# Bare_ESP32.net
KiCad netlist of a schematic drawn in EAGLE
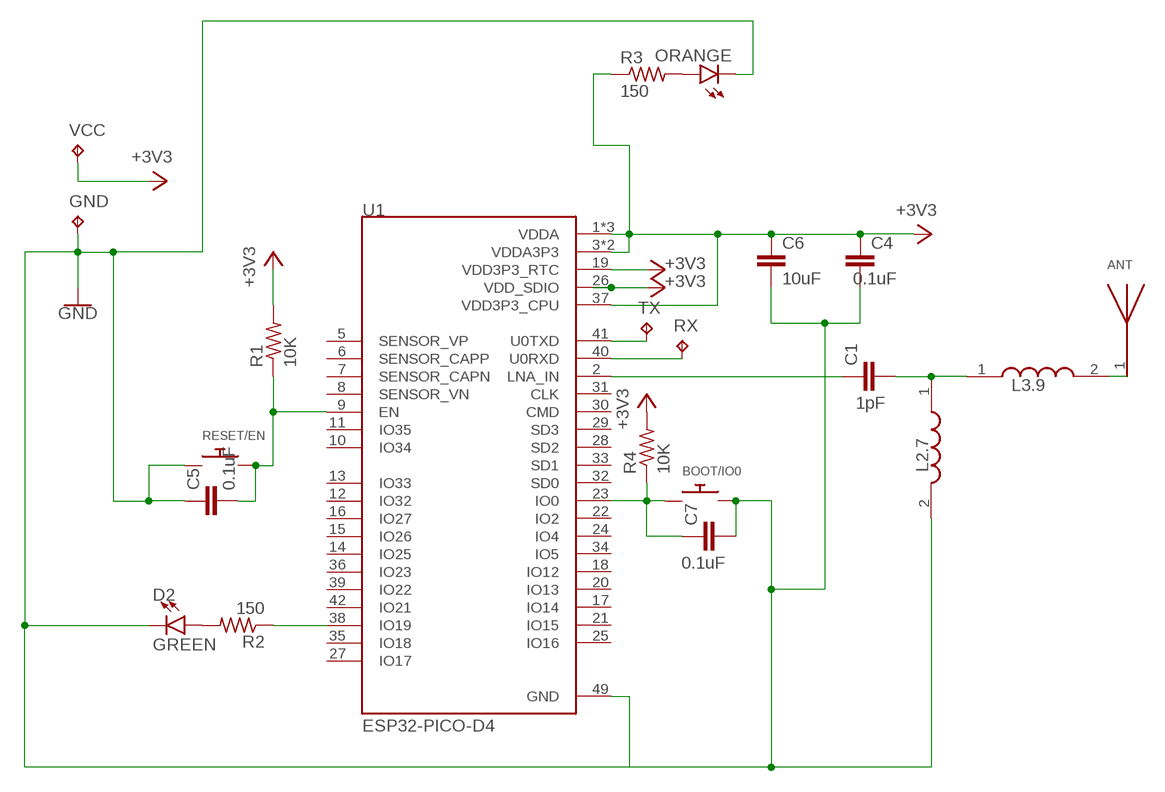
[diagram p0: schematic, sheet 1]

(export (version "E")
  (design (tool "Eeschema 10.0.6"))
  (components
    (comp (ref "ANT")
      (value "2450AT18A100E")
      (footprint "eagle-import:ANTC3216X140N")
      (fields (field (name "MF") "Johanson Technology"))
      (libsource (lib "eagle-import") (part "2450AT18A100E"))
    )
    (comp (ref "BOOT/IO0")
      (value "SWITCH_PUSHBUTTONEVQ-PE")
      (footprint "eagle-import:TACT_PANA-EVQ")
      (libsource (lib "eagle-import") (part "SWITCH_PUSHBUTTONEVQ-PE"))
    )
    (comp (ref "C1")
      (value "1pF")
      (footprint "eagle-import:0402")
      (libsource (lib "eagle-import") (part "0.1UF-0402-16V-10%"))
    )
    (comp (ref "C4")
      (value "0.1uF")
      (footprint "eagle-import:0402")
      (libsource (lib "eagle-import") (part "0.1UF-0402-16V-10%"))
    )
    (comp (ref "C5")
      (value "0.1uF")
      (footprint "eagle-import:0402")
      (libsource (lib "eagle-import") (part "0.1UF-0402-16V-10%"))
    )
    (comp (ref "C6")
      (value "10uF")
      (footprint "eagle-import:0402")
      (libsource (lib "eagle-import") (part "0.1UF-0402-16V-10%"))
    )
    (comp (ref "C7")
      (value "0.1uF")
      (footprint "eagle-import:0402")
      (libsource (lib "eagle-import") (part "0.1UF-0402-16V-10%"))
    )
    (comp (ref "D2")
      (value "GREEN")
      (footprint "eagle-import:LED-1206")
      (libsource (lib "eagle-import") (part "LED-GREEN1206"))
    )
    (comp (ref "GND")
      (value "TPTP14SQ")
      (footprint "eagle-import:TP14SQ")
      (libsource (lib "eagle-import") (part "TPTP14SQ"))
    )
    (comp (ref "L2.7")
      (value "2.7nH")
      (footprint "eagle-import:INDC1005X60N")
      (fields
        (field (name "MANUFACTURER_PART_NUMBER") "L-07C2N7SV6T")
        (field (name "MOUSER_PART_NUMBER") "609-L-07C2N7SV6T")
      )
      (libsource (lib "eagle-import") (part "L-07C2N7SV6T"))
    )
    (comp (ref "L3.9")
      (value "3.9nH")
      (footprint "eagle-import:INDC1005X60N")
      (fields
        (field (name "MANUFACTURER_PART_NUMBER") "L-07C2N7SV6T")
        (field (name "MOUSER_PART_NUMBER") "609-L-07C2N7SV6T")
      )
      (libsource (lib "eagle-import") (part "L-07C2N7SV6T"))
    )
    (comp (ref "ORANGE")
      (value "LED-ORANGE0603")
      (footprint "eagle-import:0603-ORANGE")
      (libsource (lib "eagle-import") (part "LED-ORANGE0603"))
    )
    (comp (ref "R1")
      (value "10K")
      (footprint "eagle-import:R0402")
      (libsource (lib "eagle-import") (part "R-US_R0402"))
    )
    (comp (ref "R2")
      (value "150")
      (footprint "eagle-import:R0402")
      (libsource (lib "eagle-import") (part "R-US_R0402"))
    )
    (comp (ref "R3")
      (value "150")
      (footprint "eagle-import:R0402")
      (libsource (lib "eagle-import") (part "R-US_R0402"))
    )
    (comp (ref "R4")
      (value "10K")
      (footprint "eagle-import:R0402")
      (libsource (lib "eagle-import") (part "R-US_R0402"))
    )
    (comp (ref "RESET/EN")
      (value "SWITCH_PUSHBUTTONEVQ-PE")
      (footprint "eagle-import:TACT_PANA-EVQ")
      (libsource (lib "eagle-import") (part "SWITCH_PUSHBUTTONEVQ-PE"))
    )
    (comp (ref "RX")
      (value "TPTP14SQ")
      (footprint "eagle-import:TP14SQ")
      (libsource (lib "eagle-import") (part "TPTP14SQ"))
    )
    (comp (ref "TX")
      (value "TPTP14SQ")
      (footprint "eagle-import:TP14SQ")
      (libsource (lib "eagle-import") (part "TPTP14SQ"))
    )
    (comp (ref "U1")
      (value "ESP32-PICO-D4")
      (footprint "eagle-import:PQFN50P700X700X104-49N")
      (fields (field (name "MF") "Espressif Systems"))
      (libsource (lib "eagle-import") (part "ESP32-PICO-D4"))
    )
    (comp (ref "VCC")
      (value "TPTP14SQ")
      (footprint "eagle-import:TP14SQ")
      (libsource (lib "eagle-import") (part "TPTP14SQ"))
    )
  )
  (nets
    (net (code "1") (name "+3V3") (class "Default")
      (node (ref "C4") (pin "1") (pinfunction "1_1") (pintype "passive"))
      (node (ref "C6") (pin "1") (pinfunction "1_1") (pintype "passive"))
      (node (ref "R1") (pin "2") (pinfunction "2_2") (pintype "passive"))
      (node (ref "R3") (pin "1") (pinfunction "1_1") (pintype "passive"))
      (node (ref "R4") (pin "2") (pinfunction "2_2") (pintype "passive"))
      (node (ref "U1") (pin "1") (pinfunction "VDDA_1") (pintype "power_in"))
      (node (ref "U1") (pin "19") (pinfunction "VDD3P3_RTC_19") (pintype "power_in"))
      (node (ref "U1") (pin "26") (pinfunction "VDD_SDIO_26") (pintype "power_in"))
      (node (ref "U1") (pin "3") (pinfunction "VDDA3P3_3") (pintype "power_in"))
      (node (ref "U1") (pin "37") (pinfunction "VDD3P3_CPU_37") (pintype "power_in"))
      (node (ref "U1") (pin "4") (pinfunction "VDDA3P3_4") (pintype "power_in"))
      (node (ref "U1") (pin "43") (pinfunction "VDDA_43") (pintype "power_in"))
      (node (ref "U1") (pin "46") (pinfunction "VDDA_46") (pintype "power_in"))
      (node (ref "VCC") (pin "TP") (pinfunction "TP_TP") (pintype "input"))
    )
    (net (code "2") (name "GND") (class "Default")
      (node (ref "BOOT/IO0") (pin "P$2") (pinfunction "P$2_P$2") (pintype "passive"))
      (node (ref "C4") (pin "2") (pinfunction "2_2") (pintype "passive"))
      (node (ref "C5") (pin "1") (pinfunction "1_1") (pintype "passive"))
      (node (ref "C6") (pin "2") (pinfunction "2_2") (pintype "passive"))
      (node (ref "C7") (pin "2") (pinfunction "2_2") (pintype "passive"))
      (node (ref "D2") (pin "C") (pinfunction "C_C") (pintype "passive"))
      (node (ref "GND") (pin "TP") (pinfunction "TP_TP") (pintype "input"))
      (node (ref "L2.7") (pin "2") (pinfunction "2_2") (pintype "bidirectional"))
      (node (ref "ORANGE") (pin "C") (pinfunction "C_C") (pintype "passive"))
      (node (ref "RESET/EN") (pin "P$1") (pinfunction "P$1_P$1") (pintype "passive"))
      (node (ref "U1") (pin "49") (pinfunction "GND_49") (pintype "power_in"))
    )
    (net (code "3") (name "Net-(ANT-Pad1)") (class "Default")
      (node (ref "ANT") (pin "1") (pinfunction "1_1") (pintype "input"))
      (node (ref "L3.9") (pin "2") (pinfunction "2_2") (pintype "bidirectional"))
    )
    (net (code "4") (name "Net-(C1-Pad2)") (class "Default")
      (node (ref "C1") (pin "2") (pinfunction "2_2") (pintype "passive"))
      (node (ref "L2.7") (pin "1") (pinfunction "1_1") (pintype "bidirectional"))
      (node (ref "L3.9") (pin "1") (pinfunction "1_1") (pintype "bidirectional"))
    )
    (net (code "5") (name "Net-(D2-PadA)") (class "Default")
      (node (ref "D2") (pin "A") (pinfunction "A_A") (pintype "passive"))
      (node (ref "R2") (pin "2") (pinfunction "2_2") (pintype "passive"))
    )
    (net (code "6") (name "Net-(ORANGE-PadA)") (class "Default")
      (node (ref "ORANGE") (pin "A") (pinfunction "A_A") (pintype "passive"))
      (node (ref "R3") (pin "2") (pinfunction "2_2") (pintype "passive"))
    )
    (net (code "7") (name "Net-(U1-EN)") (class "Default")
      (node (ref "C5") (pin "2") (pinfunction "2_2") (pintype "passive"))
      (node (ref "R1") (pin "1") (pinfunction "1_1") (pintype "passive"))
      (node (ref "RESET/EN") (pin "P$2") (pinfunction "P$2_P$2") (pintype "passive"))
      (node (ref "U1") (pin "9") (pinfunction "EN_9") (pintype "input"))
    )
    (net (code "8") (name "Net-(U1-IO0)") (class "Default")
      (node (ref "BOOT/IO0") (pin "P$1") (pinfunction "P$1_P$1") (pintype "passive"))
      (node (ref "C7") (pin "1") (pinfunction "1_1") (pintype "passive"))
      (node (ref "R4") (pin "1") (pinfunction "1_1") (pintype "passive"))
      (node (ref "U1") (pin "23") (pinfunction "IO0_23") (pintype "bidirectional"))
    )
    (net (code "9") (name "Net-(U1-IO19)") (class "Default")
      (node (ref "R2") (pin "1") (pinfunction "1_1") (pintype "passive"))
      (node (ref "U1") (pin "38") (pinfunction "IO19_38") (pintype "bidirectional"))
    )
    (net (code "10") (name "Net-(U1-LNA_IN)") (class "Default")
      (node (ref "C1") (pin "1") (pinfunction "1_1") (pintype "passive"))
      (node (ref "U1") (pin "2") (pinfunction "LNA_IN_2") (pintype "bidirectional"))
    )
    (net (code "11") (name "Net-(U1-U0RXD)") (class "Default")
      (node (ref "RX") (pin "TP") (pinfunction "TP_TP") (pintype "input"))
      (node (ref "U1") (pin "40") (pinfunction "U0RXD_40") (pintype "bidirectional"))
    )
    (net (code "12") (name "Net-(U1-U0TXD)") (class "Default")
      (node (ref "TX") (pin "TP") (pinfunction "TP_TP") (pintype "input"))
      (node (ref "U1") (pin "41") (pinfunction "U0TXD_41") (pintype "bidirectional"))
    )
    (net (code "13") (name "unconnected-(U1-CLK-Pad31)") (class "Default")
      (node (ref "U1") (pin "31") (pinfunction "CLK_31") (pintype "bidirectional"))
    )
    (net (code "14") (name "unconnected-(U1-CMD-Pad30)") (class "Default")
      (node (ref "U1") (pin "30") (pinfunction "CMD_30") (pintype "bidirectional"))
    )
    (net (code "15") (name "unconnected-(U1-IO2-Pad22)") (class "Default")
      (node (ref "U1") (pin "22") (pinfunction "IO2_22") (pintype "bidirectional"))
    )
    (net (code "16") (name "unconnected-(U1-IO4-Pad24)") (class "Default")
      (node (ref "U1") (pin "24") (pinfunction "IO4_24") (pintype "bidirectional"))
    )
    (net (code "17") (name "unconnected-(U1-IO5-Pad34)") (class "Default")
      (node (ref "U1") (pin "34") (pinfunction "IO5_34") (pintype "bidirectional"))
    )
    (net (code "18") (name "unconnected-(U1-IO12-Pad18)") (class "Default")
      (node (ref "U1") (pin "18") (pinfunction "IO12_18") (pintype "bidirectional"))
    )
    (net (code "19") (name "unconnected-(U1-IO13-Pad20)") (class "Default")
      (node (ref "U1") (pin "20") (pinfunction "IO13_20") (pintype "bidirectional"))
    )
    (net (code "20") (name "unconnected-(U1-IO14-Pad17)") (class "Default")
      (node (ref "U1") (pin "17") (pinfunction "IO14_17") (pintype "bidirectional"))
    )
    (net (code "21") (name "unconnected-(U1-IO15-Pad21)") (class "Default")
      (node (ref "U1") (pin "21") (pinfunction "IO15_21") (pintype "bidirectional"))
    )
    (net (code "22") (name "unconnected-(U1-IO16-Pad25)") (class "Default")
      (node (ref "U1") (pin "25") (pinfunction "IO16_25") (pintype "bidirectional"))
    )
    (net (code "23") (name "unconnected-(U1-IO17-Pad27)") (class "Default")
      (node (ref "U1") (pin "27") (pinfunction "IO17_27") (pintype "bidirectional"))
    )
    (net (code "24") (name "unconnected-(U1-IO18-Pad35)") (class "Default")
      (node (ref "U1") (pin "35") (pinfunction "IO18_35") (pintype "bidirectional"))
    )
    (net (code "25") (name "unconnected-(U1-IO21-Pad42)") (class "Default")
      (node (ref "U1") (pin "42") (pinfunction "IO21_42") (pintype "bidirectional"))
    )
    (net (code "26") (name "unconnected-(U1-IO22-Pad39)") (class "Default")
      (node (ref "U1") (pin "39") (pinfunction "IO22_39") (pintype "bidirectional"))
    )
    (net (code "27") (name "unconnected-(U1-IO23-Pad36)") (class "Default")
      (node (ref "U1") (pin "36") (pinfunction "IO23_36") (pintype "bidirectional"))
    )
    (net (code "28") (name "unconnected-(U1-IO25-Pad14)") (class "Default")
      (node (ref "U1") (pin "14") (pinfunction "IO25_14") (pintype "bidirectional"))
    )
    (net (code "29") (name "unconnected-(U1-IO26-Pad15)") (class "Default")
      (node (ref "U1") (pin "15") (pinfunction "IO26_15") (pintype "bidirectional"))
    )
    (net (code "30") (name "unconnected-(U1-IO27-Pad16)") (class "Default")
      (node (ref "U1") (pin "16") (pinfunction "IO27_16") (pintype "bidirectional"))
    )
    (net (code "31") (name "unconnected-(U1-IO32-Pad12)") (class "Default")
      (node (ref "U1") (pin "12") (pinfunction "IO32_12") (pintype "bidirectional"))
    )
    (net (code "32") (name "unconnected-(U1-IO33-Pad13)") (class "Default")
      (node (ref "U1") (pin "13") (pinfunction "IO33_13") (pintype "bidirectional"))
    )
    (net (code "33") (name "unconnected-(U1-IO34-Pad10)") (class "Default")
      (node (ref "U1") (pin "10") (pinfunction "IO34_10") (pintype "input"))
    )
    (net (code "34") (name "unconnected-(U1-IO35-Pad11)") (class "Default")
      (node (ref "U1") (pin "11") (pinfunction "IO35_11") (pintype "input"))
    )
    (net (code "35") (name "unconnected-(U1-SD0-Pad32)") (class "Default")
      (node (ref "U1") (pin "32") (pinfunction "SD0_32") (pintype "bidirectional"))
    )
    (net (code "36") (name "unconnected-(U1-SD1-Pad33)") (class "Default")
      (node (ref "U1") (pin "33") (pinfunction "SD1_33") (pintype "bidirectional"))
    )
    (net (code "37") (name "unconnected-(U1-SD2-Pad28)") (class "Default")
      (node (ref "U1") (pin "28") (pinfunction "SD2_28") (pintype "bidirectional"))
    )
    (net (code "38") (name "unconnected-(U1-SD3-Pad29)") (class "Default")
      (node (ref "U1") (pin "29") (pinfunction "SD3_29") (pintype "bidirectional"))
    )
    (net (code "39") (name "unconnected-(U1-SENSOR_CAPN-Pad7)") (class "Default")
      (node (ref "U1") (pin "7") (pinfunction "SENSOR_CAPN_7") (pintype "input"))
    )
    (net (code "40") (name "unconnected-(U1-SENSOR_CAPP-Pad6)") (class "Default")
      (node (ref "U1") (pin "6") (pinfunction "SENSOR_CAPP_6") (pintype "input"))
    )
    (net (code "41") (name "unconnected-(U1-SENSOR_VN-Pad8)") (class "Default")
      (node (ref "U1") (pin "8") (pinfunction "SENSOR_VN_8") (pintype "input"))
    )
    (net (code "42") (name "unconnected-(U1-SENSOR_VP-Pad5)") (class "Default")
      (node (ref "U1") (pin "5") (pinfunction "SENSOR_VP_5") (pintype "input"))
    )
  )
)
